# BMS.net
KiCad netlist of a schematic drawn in EAGLE
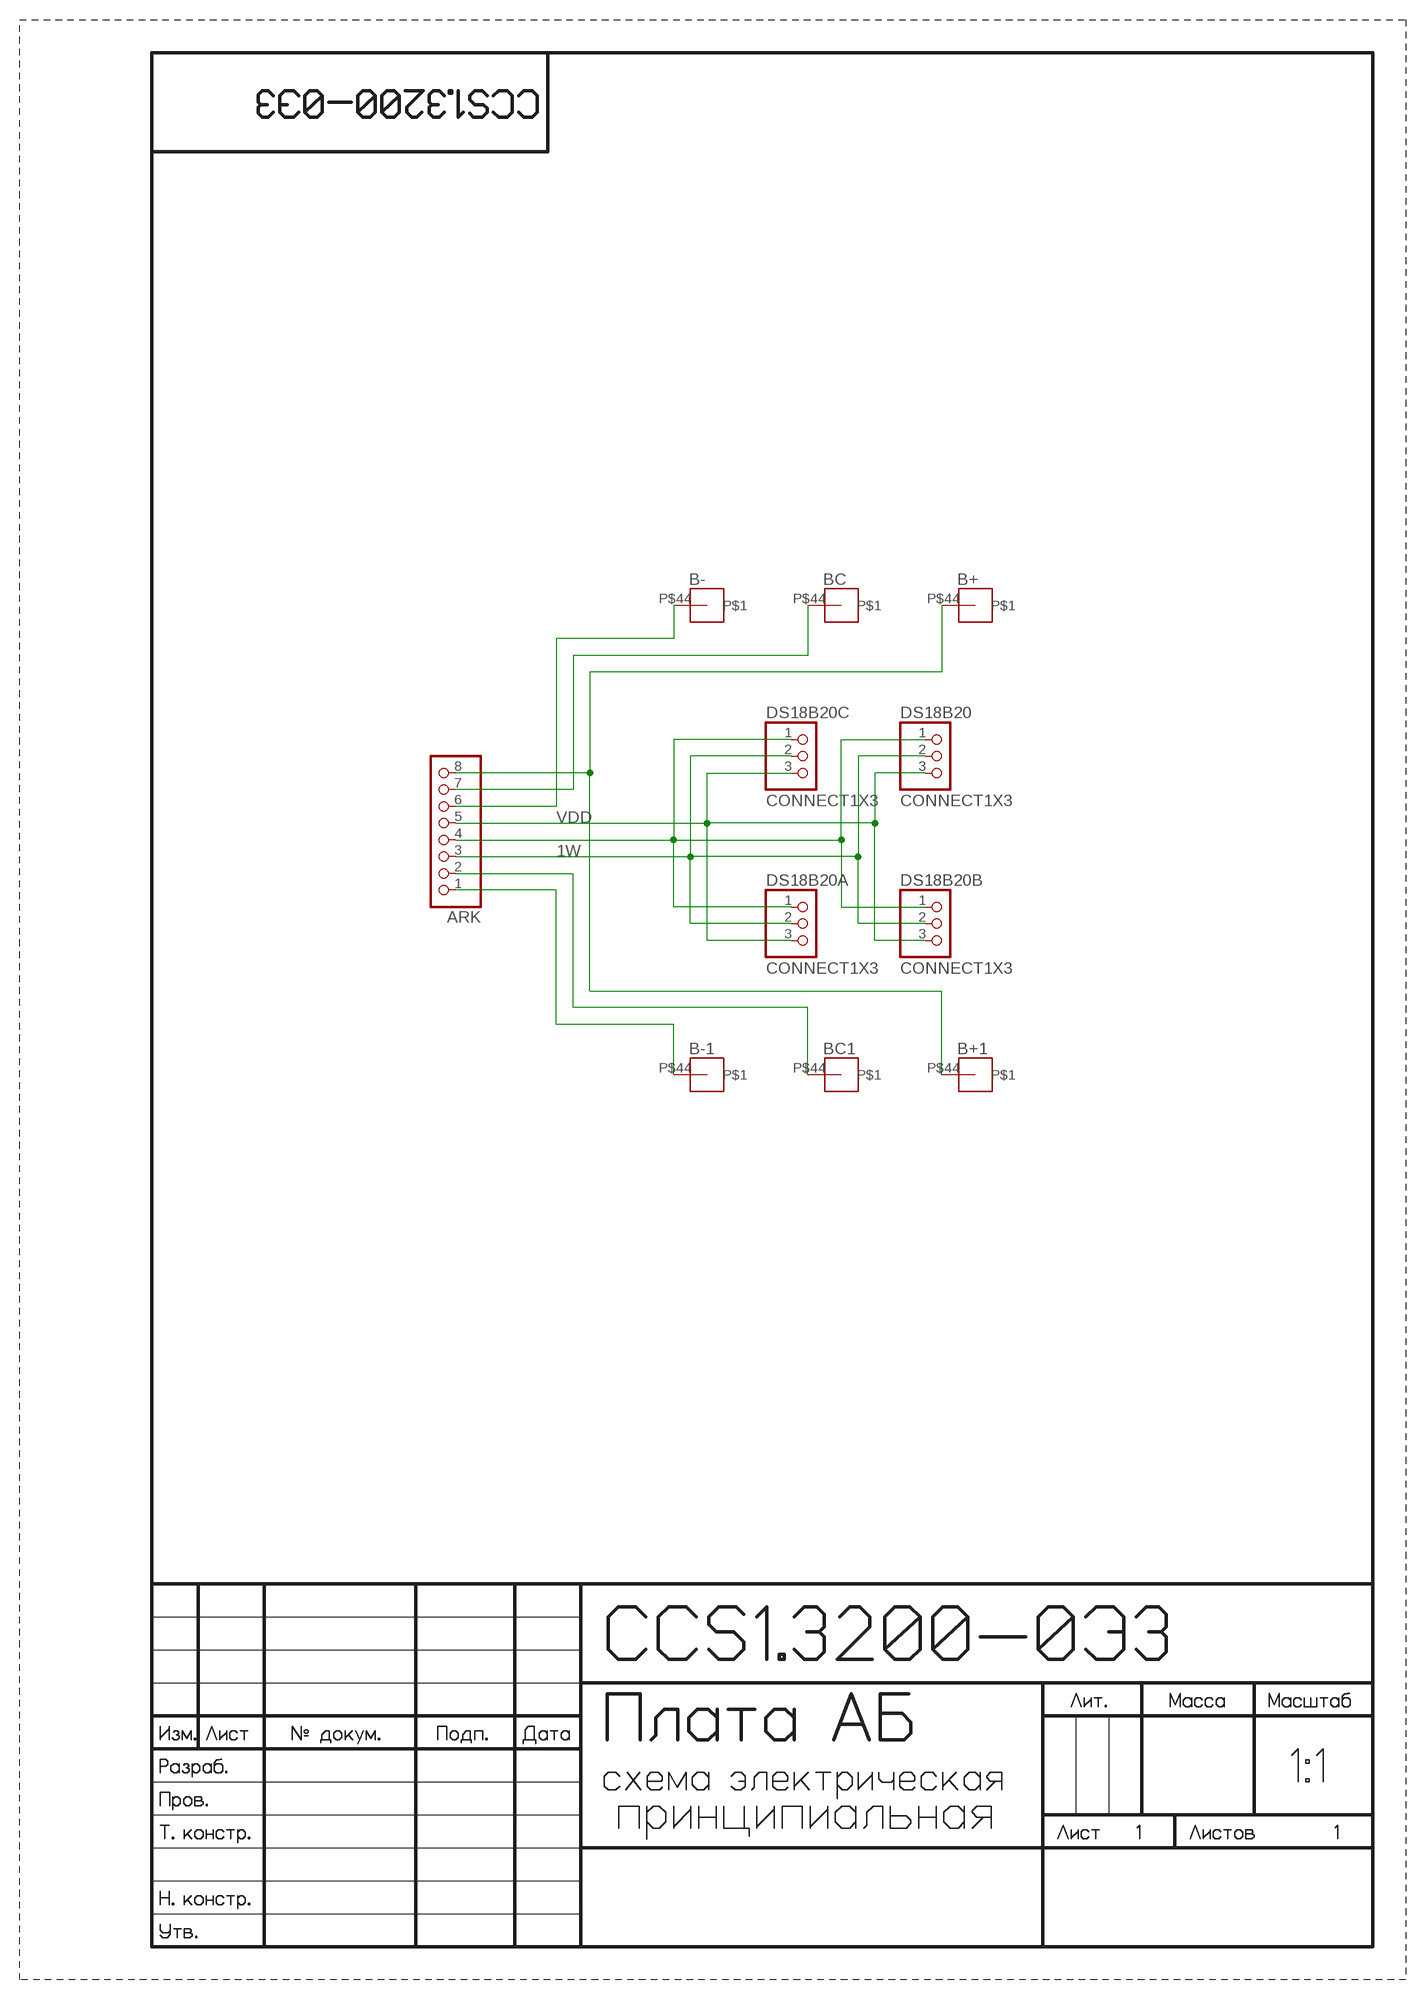
[diagram p0: schematic, sheet 1]

(export (version "E")
  (design (tool "Eeschema 10.0.6"))
  (components
    (comp (ref "ARK")
      (value "PINHD-1X8")
      (footprint "eagle-import:1X08")
      (libsource (lib "eagle-import") (part "PINHD-1X8"))
    )
    (comp (ref "B+")
      (value "DRILLBAT5")
      (footprint "eagle-import:DRILLBAT5")
      (libsource (lib "eagle-import") (part "DRILLBAT5"))
    )
    (comp (ref "B+1")
      (value "DRILLBAT5")
      (footprint "eagle-import:DRILLBAT5")
      (libsource (lib "eagle-import") (part "DRILLBAT5"))
    )
    (comp (ref "B-")
      (value "DRILLBAT5")
      (footprint "eagle-import:DRILLBAT5")
      (libsource (lib "eagle-import") (part "DRILLBAT5"))
    )
    (comp (ref "B-1")
      (value "DRILLBAT5")
      (footprint "eagle-import:DRILLBAT5")
      (libsource (lib "eagle-import") (part "DRILLBAT5"))
    )
    (comp (ref "BC")
      (value "DRILLBAT5")
      (footprint "eagle-import:DRILLBAT5")
      (libsource (lib "eagle-import") (part "DRILLBAT5"))
    )
    (comp (ref "BC1")
      (value "DRILLBAT5")
      (footprint "eagle-import:DRILLBAT5")
      (libsource (lib "eagle-import") (part "DRILLBAT5"))
    )
    (comp (ref "DS18B20")
      (value "CONNECT1X3")
      (footprint "eagle-import:CONNECT1X3")
      (libsource (lib "eagle-import") (part "CONNECT1X3"))
    )
    (comp (ref "DS18B20A")
      (value "CONNECT1X3")
      (footprint "eagle-import:CONNECT1X3")
      (libsource (lib "eagle-import") (part "CONNECT1X3"))
    )
    (comp (ref "DS18B20B")
      (value "CONNECT1X3")
      (footprint "eagle-import:CONNECT1X3")
      (libsource (lib "eagle-import") (part "CONNECT1X3"))
    )
    (comp (ref "DS18B20C")
      (value "CONNECT1X3")
      (footprint "eagle-import:CONNECT1X3")
      (libsource (lib "eagle-import") (part "CONNECT1X3"))
    )
  )
  (nets
    (net (code "1") (name "/1W") (class "Default")
      (node (ref "ARK") (pin "3") (pinfunction "3_3") (pintype "passive"))
      (node (ref "DS18B20") (pin "2") (pinfunction "2_2") (pintype "passive"))
      (node (ref "DS18B20A") (pin "2") (pinfunction "2_2") (pintype "passive"))
      (node (ref "DS18B20B") (pin "2") (pinfunction "2_2") (pintype "passive"))
      (node (ref "DS18B20C") (pin "2") (pinfunction "2_2") (pintype "passive"))
    )
    (net (code "2") (name "/VDD") (class "Default")
      (node (ref "ARK") (pin "5") (pinfunction "5_5") (pintype "passive"))
      (node (ref "DS18B20") (pin "3") (pinfunction "3_3") (pintype "passive"))
      (node (ref "DS18B20A") (pin "3") (pinfunction "3_3") (pintype "passive"))
      (node (ref "DS18B20B") (pin "3") (pinfunction "3_3") (pintype "passive"))
      (node (ref "DS18B20C") (pin "3") (pinfunction "3_3") (pintype "passive"))
    )
    (net (code "3") (name "Net-(ARK-Pad4)") (class "Default")
      (node (ref "ARK") (pin "4") (pinfunction "4_4") (pintype "passive"))
      (node (ref "DS18B20") (pin "1") (pinfunction "1_1") (pintype "passive"))
      (node (ref "DS18B20A") (pin "1") (pinfunction "1_1") (pintype "passive"))
      (node (ref "DS18B20B") (pin "1") (pinfunction "1_1") (pintype "passive"))
      (node (ref "DS18B20C") (pin "1") (pinfunction "1_1") (pintype "passive"))
    )
    (net (code "4") (name "Net-(B+-P$1)") (class "Default")
      (node (ref "ARK") (pin "8") (pinfunction "8_8") (pintype "passive"))
      (node (ref "B+") (pin "P$44") (pinfunction "P$1_P$44") (pintype "bidirectional"))
      (node (ref "B+1") (pin "P$44") (pinfunction "P$1_P$44") (pintype "bidirectional"))
    )
    (net (code "5") (name "Net-(B--P$1)") (class "Default")
      (node (ref "ARK") (pin "6") (pinfunction "6_6") (pintype "passive"))
      (node (ref "B-") (pin "P$44") (pinfunction "P$1_P$44") (pintype "bidirectional"))
    )
    (net (code "6") (name "Net-(B-1-P$1)") (class "Default")
      (node (ref "ARK") (pin "1") (pinfunction "1_1") (pintype "passive"))
      (node (ref "B-1") (pin "P$44") (pinfunction "P$1_P$44") (pintype "bidirectional"))
    )
    (net (code "7") (name "Net-(BC-P$1)") (class "Default")
      (node (ref "ARK") (pin "7") (pinfunction "7_7") (pintype "passive"))
      (node (ref "BC") (pin "P$44") (pinfunction "P$1_P$44") (pintype "bidirectional"))
    )
    (net (code "8") (name "Net-(BC1-P$1)") (class "Default")
      (node (ref "ARK") (pin "2") (pinfunction "2_2") (pintype "passive"))
      (node (ref "BC1") (pin "P$44") (pinfunction "P$1_P$44") (pintype "bidirectional"))
    )
  )
)
